# GPS.net
KiCad netlist of a schematic drawn in Altium Designer
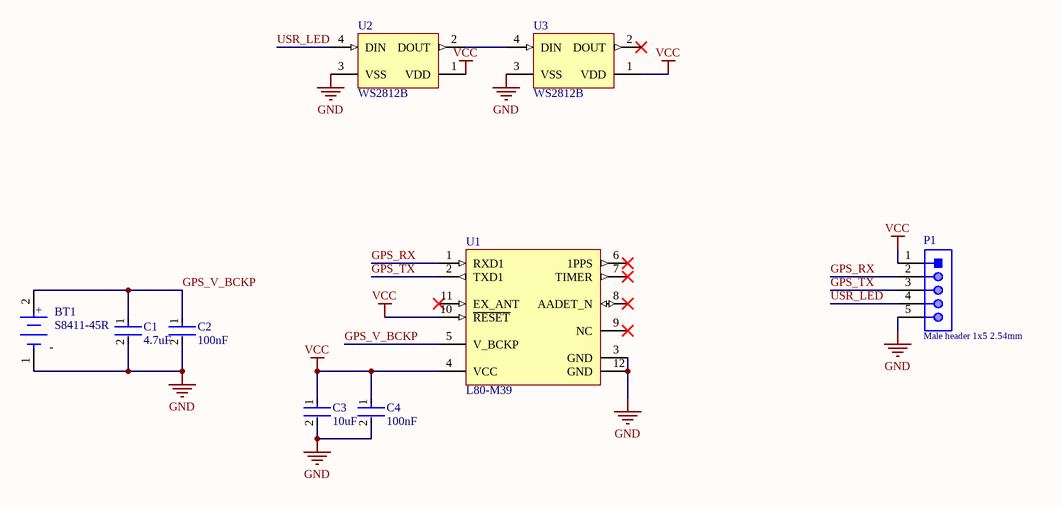
[diagram p0: GPS.SchDoc]

(export (version "E")
  (design (tool "Eeschema 10.0.6"))
  (components
    (comp (ref "BT1")
      (value "S8411-45R")
      (footprint "FP-S8411-45R-MFG")
      (description "EZ-Coin Cell Battery Retainer, Horizontal SMT, for CR1220 Coin Cell Batteries")
      (libsource (lib "StrathSEDS") (part "60d3b5b901a8747834971d0eb8cf3fd"))
    )
    (comp (ref "C1")
      (value "4.7uF")
      (footprint "FP-0603-L_1_6_0_15-W_0_81-IPC_C")
      (description "Generic 0603 Capacitor")
      (fields (field (name "LCSC PART #") "C19666") (field (name "TOLERANCE") "10%"))
      (libsource (lib "StrathSEDS") (part "02cd4be3c70576c341d710602a673aa"))
    )
    (comp (ref "C2")
      (value "100nF")
      (footprint "FP-0603-L_1_6_0_15-W_0_81-IPC_C")
      (description "Generic 0603 Capacitor")
      (fields (field (name "LCSC PART #") "C14663") (field (name "TOLERANCE") "10%"))
      (libsource (lib "StrathSEDS") (part "02cd4be3c70576c341d710602a673aa"))
    )
    (comp (ref "C3")
      (value "10uF")
      (footprint "FP-0603-L_1_6_0_15-W_0_81-IPC_C")
      (description "Generic 0603 Capacitor")
      (fields (field (name "LCSC PART #") "C96446") (field (name "TOLERANCE") "10%"))
      (libsource (lib "StrathSEDS") (part "02cd4be3c70576c341d710602a673aa"))
    )
    (comp (ref "C4")
      (value "100nF")
      (footprint "FP-0603-L_1_6_0_15-W_0_81-IPC_C")
      (description "Generic 0603 Capacitor")
      (fields (field (name "LCSC PART #") "C14663") (field (name "TOLERANCE") "10%"))
      (libsource (lib "StrathSEDS") (part "02cd4be3c70576c341d710602a673aa"))
    )
    (comp (ref "P1")
      (value "Male header 1x5 2.54mm")
      (footprint "61300511121")
      (description "THT Vertical Pin Header WR-PHD, Pitch 2.54 mm, Single Row, 5 pins")
      (libsource (lib "StrathSEDS") (part "WE-CN-1P-M-R5"))
    )
    (comp (ref "U1")
      (value "L80-M39")
      (footprint "QUEC-L80-M39-12_V")
      (description "GPS Module 15, 0x15, 0x4, 0mm SMD w/Antenna 3, 0V")
      (libsource (lib "StrathSEDS") (part "QUEC-L80-M39-12"))
    )
    (comp (ref "U2")
      (value "WS2812B")
      (footprint "ADAI-WS2812B_V")
      (fields (field (name "MANUFACTURER") "Adafruit Industries") (field (name "LCSC PART #") "C4154882"))
      (libsource (lib "StrathSEDS") (part "ADAI-WS2812B-4"))
    )
    (comp (ref "U3")
      (value "WS2812B")
      (footprint "ADAI-WS2812B_V")
      (fields (field (name "MANUFACTURER") "Adafruit Industries") (field (name "LCSC PART #") "C4154882"))
      (libsource (lib "StrathSEDS") (part "ADAI-WS2812B-4"))
    )
  )
  (nets
    (net (code "1") (name "/GPS_RX") (class "Default")
      (node (ref "P1") (pin "2") (pinfunction "2_2") (pintype "passive"))
      (node (ref "U1") (pin "1") (pinfunction "RXD1_1") (pintype "input"))
    )
    (net (code "2") (name "/GPS_TX") (class "Default")
      (node (ref "P1") (pin "3") (pinfunction "3_3") (pintype "passive"))
      (node (ref "U1") (pin "2") (pinfunction "TXD1_2") (pintype "output"))
    )
    (net (code "3") (name "/GPS_V_BCKP") (class "Default")
      (node (ref "BT1") (pin "2") (pinfunction "A_2") (pintype "passive"))
      (node (ref "C1") (pin "1") (pinfunction "1_1") (pintype "passive"))
      (node (ref "C2") (pin "1") (pinfunction "1_1") (pintype "passive"))
      (node (ref "U1") (pin "5") (pinfunction "V_BCKP_5") (pintype "power_in"))
    )
    (net (code "4") (name "/USR_LED") (class "Default")
      (node (ref "P1") (pin "4") (pinfunction "4_4") (pintype "passive"))
      (node (ref "U2") (pin "4") (pinfunction "DIN_4") (pintype "input"))
    )
    (net (code "5") (name "GND") (class "Default")
      (node (ref "BT1") (pin "1") (pinfunction "C_1") (pintype "passive"))
      (node (ref "C1") (pin "2") (pinfunction "2_2") (pintype "passive"))
      (node (ref "C2") (pin "2") (pinfunction "2_2") (pintype "passive"))
      (node (ref "C3") (pin "2") (pinfunction "2_2") (pintype "passive"))
      (node (ref "C4") (pin "2") (pinfunction "2_2") (pintype "passive"))
      (node (ref "P1") (pin "5") (pinfunction "5_5") (pintype "passive"))
      (node (ref "U1") (pin "12") (pinfunction "GND_12") (pintype "power_in"))
      (node (ref "U1") (pin "3") (pinfunction "GND_3") (pintype "power_in"))
      (node (ref "U2") (pin "3") (pinfunction "VSS_3") (pintype "power_in"))
      (node (ref "U3") (pin "3") (pinfunction "VSS_3") (pintype "power_in"))
    )
    (net (code "6") (name "Net-(U2-DOUT)") (class "Default")
      (node (ref "U2") (pin "2") (pinfunction "DOUT_2") (pintype "output"))
      (node (ref "U3") (pin "4") (pinfunction "DIN_4") (pintype "input"))
    )
    (net (code "7") (name "VCC") (class "Default")
      (node (ref "C3") (pin "1") (pinfunction "1_1") (pintype "passive"))
      (node (ref "C4") (pin "1") (pinfunction "1_1") (pintype "passive"))
      (node (ref "P1") (pin "1") (pinfunction "1_1") (pintype "passive"))
      (node (ref "U1") (pin "10") (pinfunction "~{RESET}_10") (pintype "input"))
      (node (ref "U1") (pin "4") (pinfunction "VCC_4") (pintype "power_in"))
      (node (ref "U2") (pin "1") (pinfunction "VDD_1") (pintype "power_in"))
      (node (ref "U3") (pin "1") (pinfunction "VDD_1") (pintype "power_in"))
    )
    (net (code "8") (name "unconnected-(U1-1PPS-Pad6)") (class "Default")
      (node (ref "U1") (pin "6") (pinfunction "1PPS_6") (pintype "output+no_connect"))
    )
    (net (code "9") (name "unconnected-(U1-AADET_N-Pad8)") (class "Default")
      (node (ref "U1") (pin "8") (pinfunction "AADET_N_8") (pintype "bidirectional+no_connect"))
    )
    (net (code "10") (name "unconnected-(U1-EX_ANT-Pad11)") (class "Default")
      (node (ref "U1") (pin "11") (pinfunction "EX_ANT_11") (pintype "input+no_connect"))
    )
    (net (code "11") (name "unconnected-(U1-NC-Pad9)") (class "Default")
      (node (ref "U1") (pin "9") (pinfunction "NC_9") (pintype "passive+no_connect"))
    )
    (net (code "12") (name "unconnected-(U1-TIMER-Pad7)") (class "Default")
      (node (ref "U1") (pin "7") (pinfunction "TIMER_7") (pintype "output+no_connect"))
    )
    (net (code "13") (name "unconnected-(U3-DOUT-Pad2)") (class "Default")
      (node (ref "U3") (pin "2") (pinfunction "DOUT_2") (pintype "output+no_connect"))
    )
  )
)
